# Relay_2_Board_v1_0.net
KiCad netlist of a schematic drawn in EAGLE
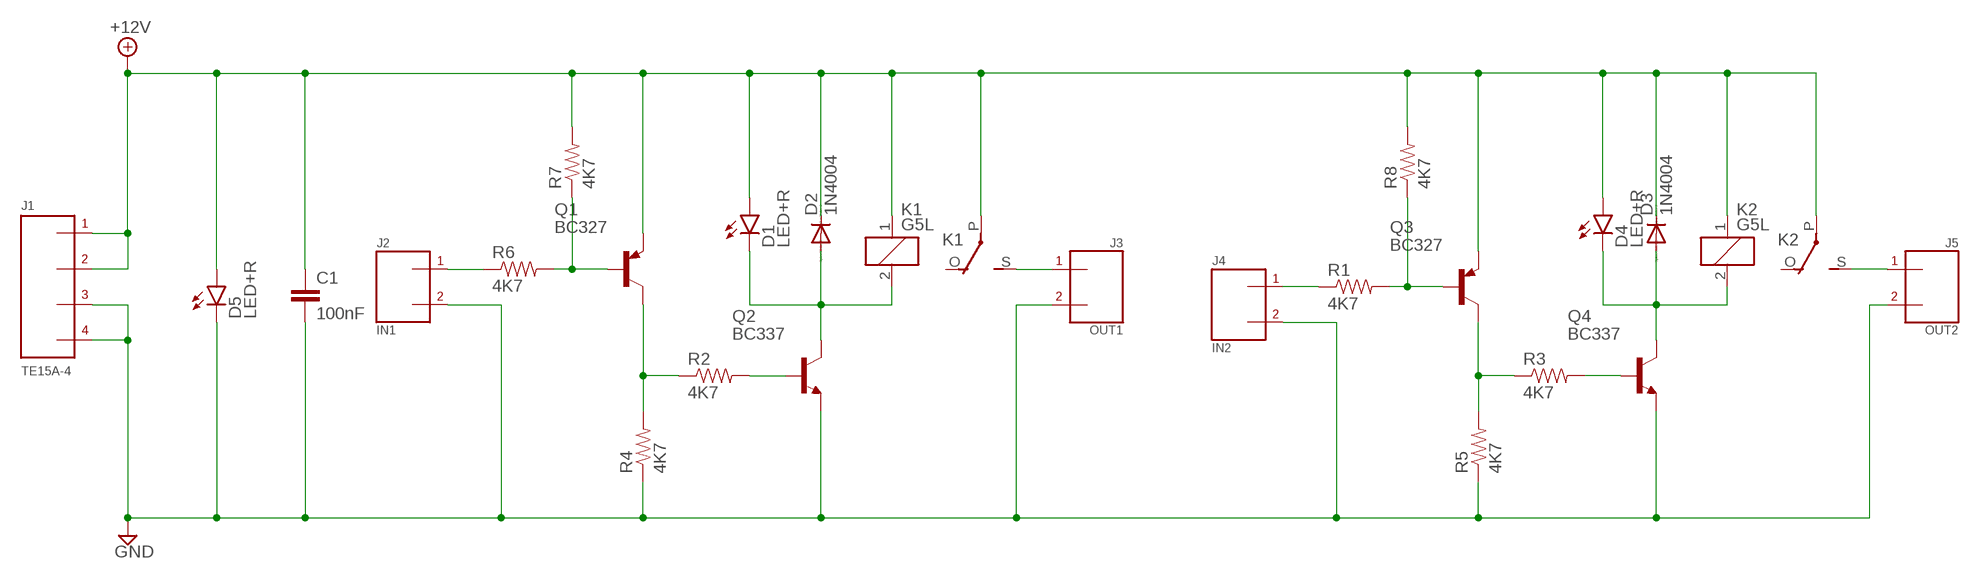
[diagram p0: schematic, sheet 1]

(export (version "E")
  (design (tool "Eeschema 10.0.6"))
  (components
    (comp (ref "C1")
      (value "100nF")
      (footprint "eagle-import:CAP-PTH-5MM")
      (libsource (lib "eagle-import") (part "CAPPTH1"))
    )
    (comp (ref "D1")
      (value "LED+R")
      (footprint "eagle-import:LED3MM")
      (libsource (lib "eagle-import") (part "LED3MM"))
    )
    (comp (ref "D2")
      (value "1N4004")
      (footprint "eagle-import:DO41-10")
      (libsource (lib "eagle-import") (part "1N4004"))
    )
    (comp (ref "D3")
      (value "1N4004")
      (footprint "eagle-import:DO41-10")
      (libsource (lib "eagle-import") (part "1N4004"))
    )
    (comp (ref "D4")
      (value "LED+R")
      (footprint "eagle-import:LED3MM")
      (libsource (lib "eagle-import") (part "LED3MM"))
    )
    (comp (ref "D5")
      (value "LED+R")
      (footprint "eagle-import:LED3MM")
      (libsource (lib "eagle-import") (part "LED3MM"))
    )
    (comp (ref "J1")
      (value "TE15A-4")
      (footprint "eagle-import:J4-950MM")
      (libsource (lib "eagle-import") (part "TE15A-4"))
    )
    (comp (ref "J2")
      (value "IN1")
      (footprint "eagle-import:J2V-508MM")
      (libsource (lib "eagle-import") (part "J2-508MMV"))
    )
    (comp (ref "J3")
      (value "OUT1")
      (footprint "eagle-import:J2V-508MM")
      (libsource (lib "eagle-import") (part "J2-508MMV"))
    )
    (comp (ref "J4")
      (value "IN2")
      (footprint "eagle-import:J2V-508MM")
      (libsource (lib "eagle-import") (part "J2-508MMV"))
    )
    (comp (ref "J5")
      (value "OUT2")
      (footprint "eagle-import:J2V-508MM")
      (libsource (lib "eagle-import") (part "J2-508MMV"))
    )
    (comp (ref "K1")
      (value "G5L")
      (footprint "eagle-import:G5LE")
      (libsource (lib "eagle-import") (part "G5L"))
    )
    (comp (ref "K2")
      (value "G5L")
      (footprint "eagle-import:G5LE")
      (libsource (lib "eagle-import") (part "G5L"))
    )
    (comp (ref "Q1")
      (value "BC327")
      (footprint "eagle-import:TO92")
      (libsource (lib "eagle-import") (part "BC327"))
    )
    (comp (ref "Q2")
      (value "BC337")
      (footprint "eagle-import:TO92")
      (libsource (lib "eagle-import") (part "BC337"))
    )
    (comp (ref "Q3")
      (value "BC327")
      (footprint "eagle-import:TO92")
      (libsource (lib "eagle-import") (part "BC327"))
    )
    (comp (ref "Q4")
      (value "BC337")
      (footprint "eagle-import:TO92")
      (libsource (lib "eagle-import") (part "BC337"))
    )
    (comp (ref "R1")
      (value "4K7")
      (footprint "eagle-import:AXIAL-0.3")
      (libsource (lib "eagle-import") (part "RESISTORAXIAL-0.3"))
    )
    (comp (ref "R2")
      (value "4K7")
      (footprint "eagle-import:AXIAL-0.3")
      (libsource (lib "eagle-import") (part "RESISTORAXIAL-0.3"))
    )
    (comp (ref "R3")
      (value "4K7")
      (footprint "eagle-import:AXIAL-0.3")
      (libsource (lib "eagle-import") (part "RESISTORAXIAL-0.3"))
    )
    (comp (ref "R4")
      (value "4K7")
      (footprint "eagle-import:AXIAL-0.3")
      (libsource (lib "eagle-import") (part "RESISTORAXIAL-0.3"))
    )
    (comp (ref "R5")
      (value "4K7")
      (footprint "eagle-import:AXIAL-0.3")
      (libsource (lib "eagle-import") (part "RESISTORAXIAL-0.3"))
    )
    (comp (ref "R6")
      (value "4K7")
      (footprint "eagle-import:AXIAL-0.3")
      (libsource (lib "eagle-import") (part "RESISTORAXIAL-0.3"))
    )
    (comp (ref "R7")
      (value "4K7")
      (footprint "eagle-import:AXIAL-0.3")
      (libsource (lib "eagle-import") (part "RESISTORAXIAL-0.3"))
    )
    (comp (ref "R8")
      (value "4K7")
      (footprint "eagle-import:AXIAL-0.3")
      (libsource (lib "eagle-import") (part "RESISTORAXIAL-0.3"))
    )
  )
  (nets
    (net (code "1") (name "+12V") (class "Default")
      (node (ref "C1") (pin "1") (pinfunction "1_1") (pintype "passive"))
      (node (ref "D1") (pin "A") (pinfunction "A_A") (pintype "passive"))
      (node (ref "D2") (pin "C") (pinfunction "C_C") (pintype "passive"))
      (node (ref "D3") (pin "C") (pinfunction "C_C") (pintype "passive"))
      (node (ref "D4") (pin "A") (pinfunction "A_A") (pintype "passive"))
      (node (ref "D5") (pin "A") (pinfunction "A_A") (pintype "passive"))
      (node (ref "J1") (pin "P$1") (pinfunction "1_P$1") (pintype "bidirectional"))
      (node (ref "J1") (pin "P$2") (pinfunction "2_P$2") (pintype "bidirectional"))
      (node (ref "K1") (pin "1") (pinfunction "1_1") (pintype "passive"))
      (node (ref "K1") (pin "P") (pinfunction "P_P") (pintype "passive"))
      (node (ref "K2") (pin "1") (pinfunction "1_1") (pintype "passive"))
      (node (ref "K2") (pin "P") (pinfunction "P_P") (pintype "passive"))
      (node (ref "Q1") (pin "1") (pinfunction "E_1") (pintype "passive"))
      (node (ref "Q3") (pin "1") (pinfunction "E_1") (pintype "passive"))
      (node (ref "R7") (pin "P$2") (pinfunction "2_P$2") (pintype "passive"))
      (node (ref "R8") (pin "P$2") (pinfunction "2_P$2") (pintype "passive"))
    )
    (net (code "2") (name "GND") (class "Default")
      (node (ref "C1") (pin "2") (pinfunction "2_2") (pintype "passive"))
      (node (ref "D5") (pin "K") (pinfunction "C_K") (pintype "passive"))
      (node (ref "J1") (pin "P$3") (pinfunction "3_P$3") (pintype "bidirectional"))
      (node (ref "J1") (pin "P$4") (pinfunction "4_P$4") (pintype "bidirectional"))
      (node (ref "J2") (pin "P$2") (pinfunction "P$2_P$2") (pintype "bidirectional"))
      (node (ref "J3") (pin "P$2") (pinfunction "P$2_P$2") (pintype "bidirectional"))
      (node (ref "J4") (pin "P$2") (pinfunction "P$2_P$2") (pintype "bidirectional"))
      (node (ref "J5") (pin "P$2") (pinfunction "P$2_P$2") (pintype "bidirectional"))
      (node (ref "Q2") (pin "1") (pinfunction "E_1") (pintype "passive"))
      (node (ref "Q4") (pin "1") (pinfunction "E_1") (pintype "passive"))
      (node (ref "R4") (pin "P$1") (pinfunction "1_P$1") (pintype "passive"))
      (node (ref "R5") (pin "P$1") (pinfunction "1_P$1") (pintype "passive"))
    )
    (net (code "3") (name "Net-(D1-C)") (class "Default")
      (node (ref "D1") (pin "K") (pinfunction "C_K") (pintype "passive"))
      (node (ref "D2") (pin "A") (pinfunction "A_A") (pintype "passive"))
      (node (ref "K1") (pin "2") (pinfunction "2_2") (pintype "passive"))
      (node (ref "Q2") (pin "3") (pinfunction "C_3") (pintype "passive"))
    )
    (net (code "4") (name "Net-(D4-C)") (class "Default")
      (node (ref "D3") (pin "A") (pinfunction "A_A") (pintype "passive"))
      (node (ref "D4") (pin "K") (pinfunction "C_K") (pintype "passive"))
      (node (ref "K2") (pin "2") (pinfunction "2_2") (pintype "passive"))
      (node (ref "Q4") (pin "3") (pinfunction "C_3") (pintype "passive"))
    )
    (net (code "5") (name "Net-(J3-PadP$1)") (class "Default")
      (node (ref "J3") (pin "P$1") (pinfunction "P$1_P$1") (pintype "bidirectional"))
      (node (ref "K1") (pin "S") (pinfunction "S_S") (pintype "passive"))
    )
    (net (code "6") (name "Net-(J5-PadP$1)") (class "Default")
      (node (ref "J5") (pin "P$1") (pinfunction "P$1_P$1") (pintype "bidirectional"))
      (node (ref "K2") (pin "S") (pinfunction "S_S") (pintype "passive"))
    )
    (net (code "7") (name "Net-(Q1-B)") (class "Default")
      (node (ref "Q1") (pin "2") (pinfunction "B_2") (pintype "passive"))
      (node (ref "R6") (pin "P$2") (pinfunction "2_P$2") (pintype "passive"))
      (node (ref "R7") (pin "P$1") (pinfunction "1_P$1") (pintype "passive"))
    )
    (net (code "8") (name "Net-(Q1-C)") (class "Default")
      (node (ref "Q1") (pin "3") (pinfunction "C_3") (pintype "passive"))
      (node (ref "R2") (pin "P$1") (pinfunction "1_P$1") (pintype "passive"))
      (node (ref "R4") (pin "P$2") (pinfunction "2_P$2") (pintype "passive"))
    )
    (net (code "9") (name "Net-(Q2-B)") (class "Default")
      (node (ref "Q2") (pin "2") (pinfunction "B_2") (pintype "passive"))
      (node (ref "R2") (pin "P$2") (pinfunction "2_P$2") (pintype "passive"))
    )
    (net (code "10") (name "Net-(Q3-B)") (class "Default")
      (node (ref "Q3") (pin "2") (pinfunction "B_2") (pintype "passive"))
      (node (ref "R1") (pin "P$2") (pinfunction "2_P$2") (pintype "passive"))
      (node (ref "R8") (pin "P$1") (pinfunction "1_P$1") (pintype "passive"))
    )
    (net (code "11") (name "Net-(Q3-C)") (class "Default")
      (node (ref "Q3") (pin "3") (pinfunction "C_3") (pintype "passive"))
      (node (ref "R3") (pin "P$1") (pinfunction "1_P$1") (pintype "passive"))
      (node (ref "R5") (pin "P$2") (pinfunction "2_P$2") (pintype "passive"))
    )
    (net (code "12") (name "Net-(Q4-B)") (class "Default")
      (node (ref "Q4") (pin "2") (pinfunction "B_2") (pintype "passive"))
      (node (ref "R3") (pin "P$2") (pinfunction "2_P$2") (pintype "passive"))
    )
    (net (code "13") (name "Net-(R1-1)") (class "Default")
      (node (ref "J4") (pin "P$1") (pinfunction "P$1_P$1") (pintype "bidirectional"))
      (node (ref "R1") (pin "P$1") (pinfunction "1_P$1") (pintype "passive"))
    )
    (net (code "14") (name "Net-(R6-1)") (class "Default")
      (node (ref "J2") (pin "P$1") (pinfunction "P$1_P$1") (pintype "bidirectional"))
      (node (ref "R6") (pin "P$1") (pinfunction "1_P$1") (pintype "passive"))
    )
    (net (code "15") (name "unconnected-(K1-PadO)") (class "Default")
      (node (ref "K1") (pin "O") (pinfunction "O_O") (pintype "passive"))
    )
    (net (code "16") (name "unconnected-(K2-PadO)") (class "Default")
      (node (ref "K2") (pin "O") (pinfunction "O_O") (pintype "passive"))
    )
  )
)
